# laserBordMain.net
KiCad netlist of a schematic drawn in EasyEDA Pro
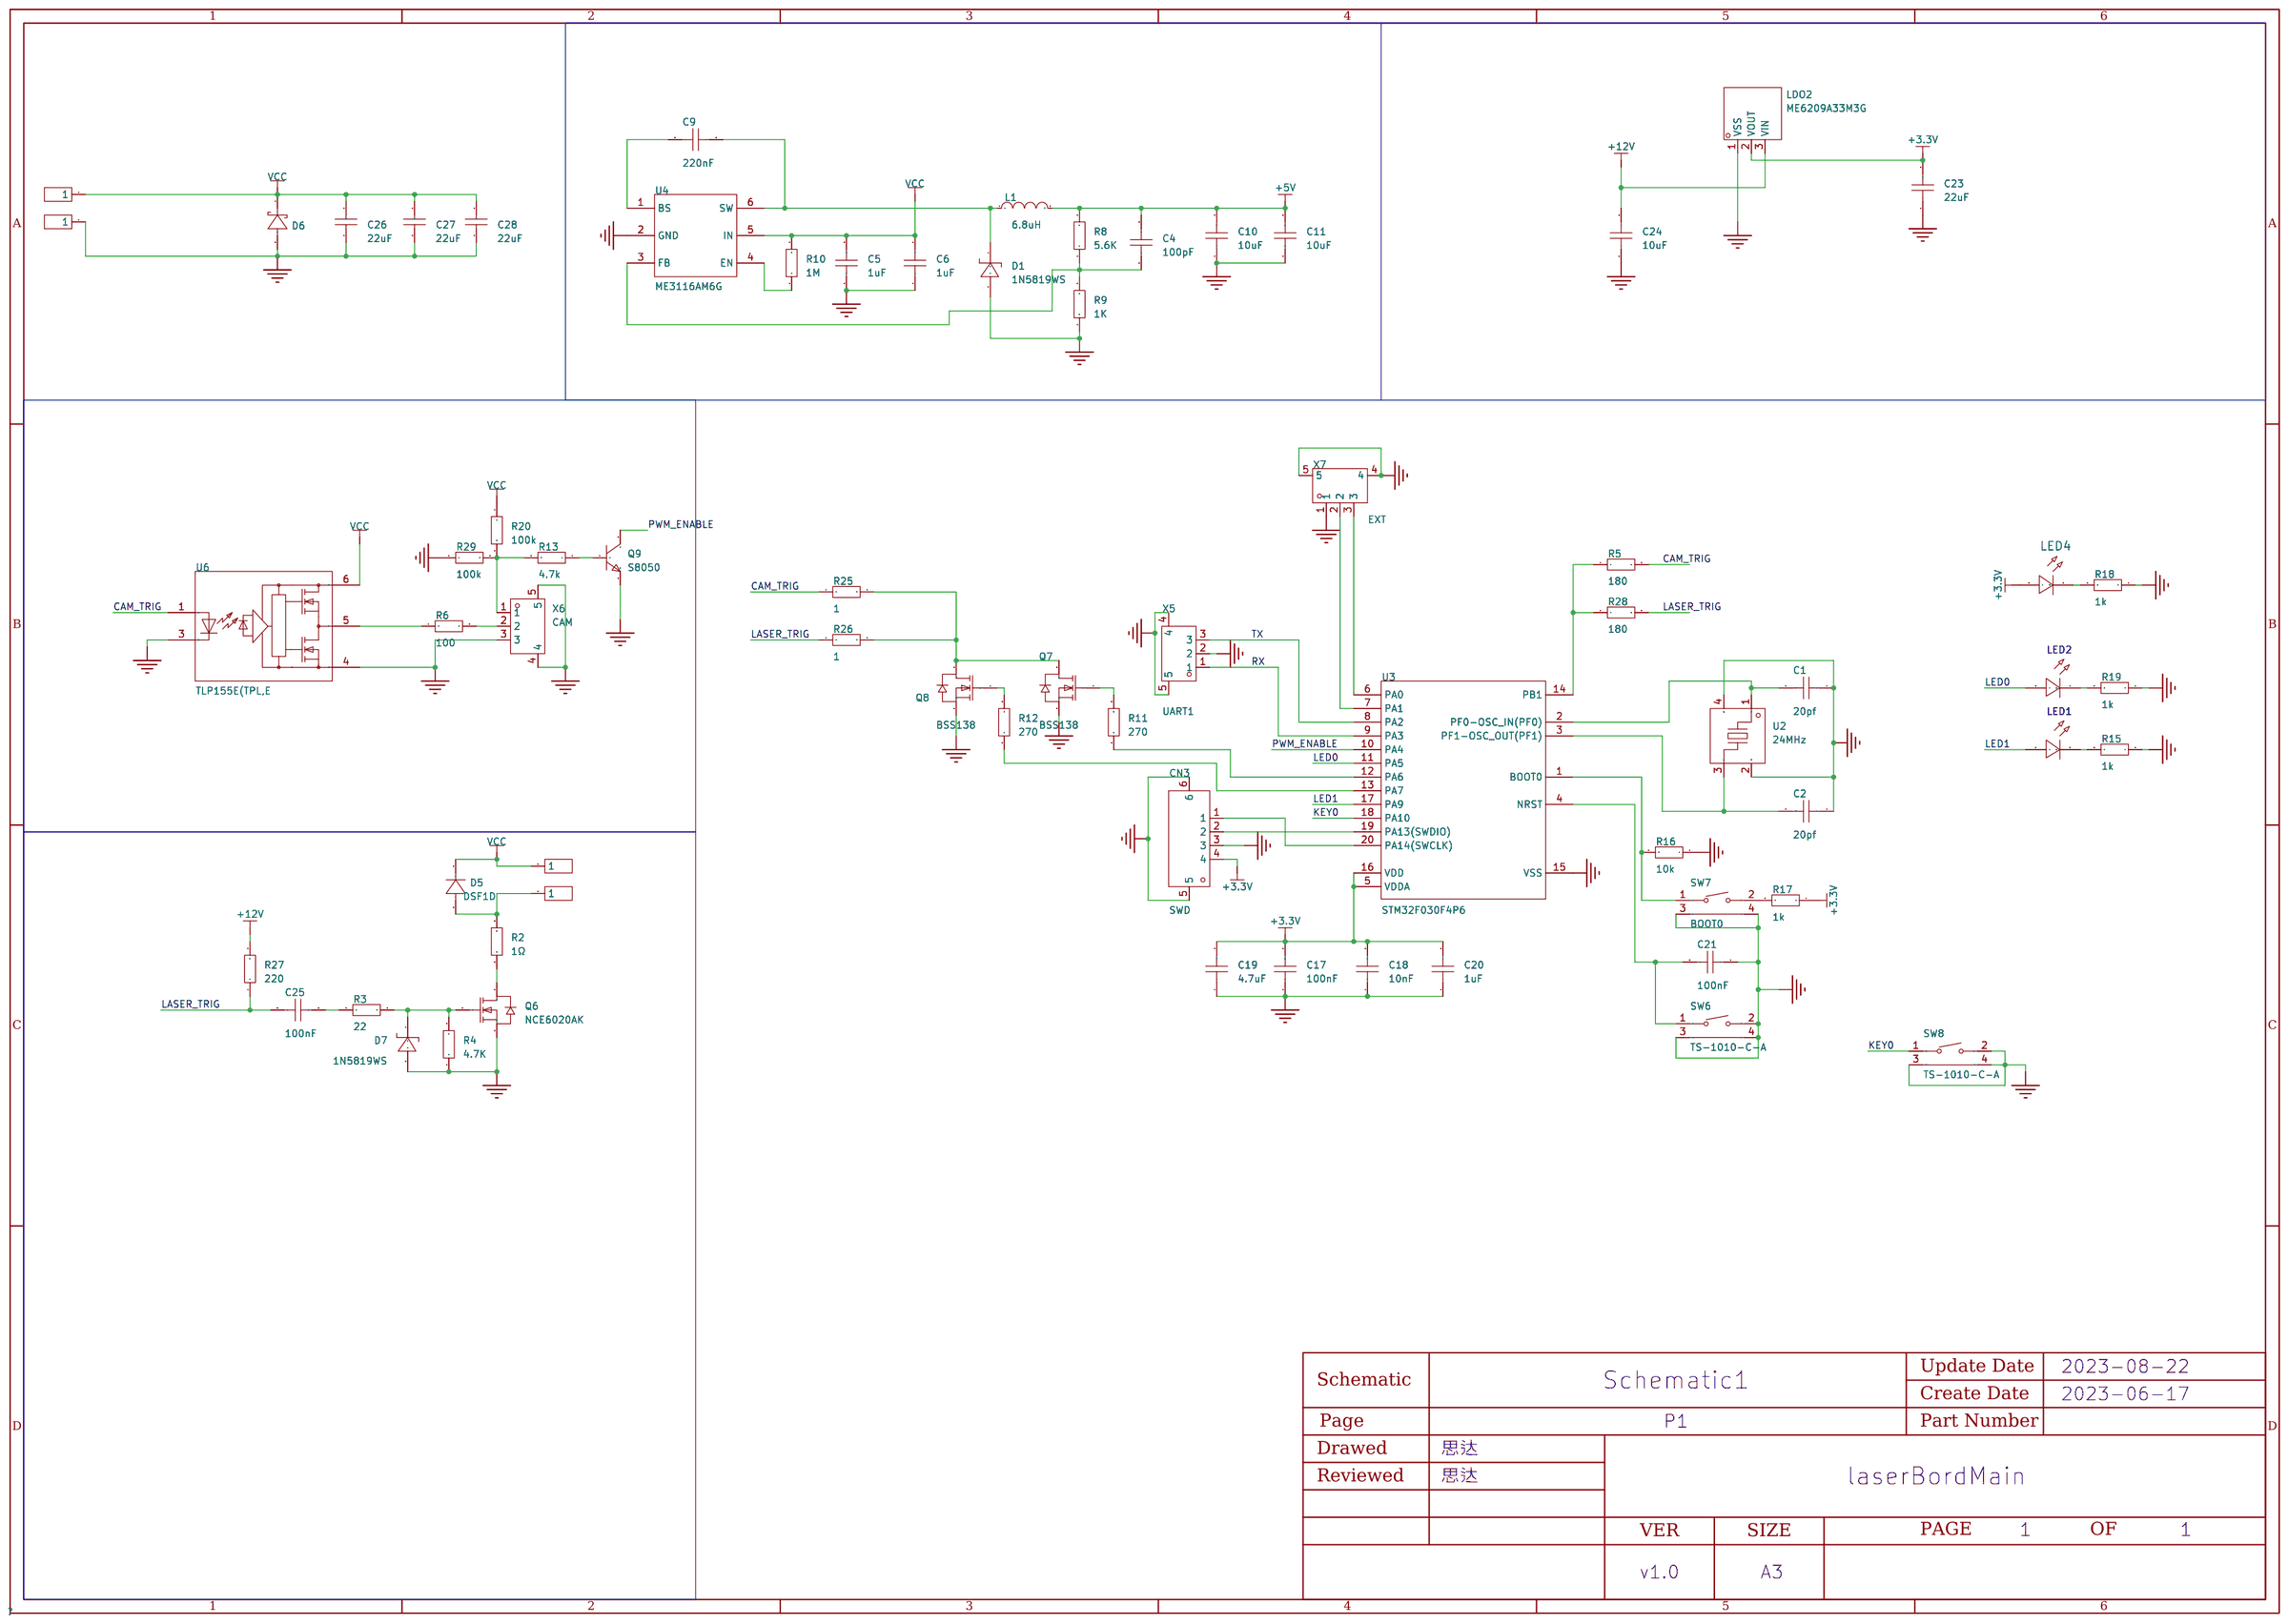
[diagram p0: schematic sheet]

(export (version "E")
  (design (tool "Eeschema 10.0.6"))
  (components
    (comp (ref "C1")
      (value "20pf")
      (footprint "easyedapro:C0603")
      (libsource (lib "easyedapro") (part "CapAcitance"))
    )
    (comp (ref "C2")
      (value "20pf")
      (footprint "easyedapro:C0603")
      (libsource (lib "easyedapro") (part "CapAcitance"))
    )
    (comp (ref "C4")
      (value "100pF")
      (footprint "easyedapro:C0603")
      (libsource (lib "easyedapro") (part "CapAcitance"))
    )
    (comp (ref "C5")
      (value "1uF")
      (footprint "easyedapro:C0603")
      (libsource (lib "easyedapro") (part "CapAcitance"))
    )
    (comp (ref "C6")
      (value "1uF")
      (footprint "easyedapro:C0603")
      (libsource (lib "easyedapro") (part "CapAcitance"))
    )
    (comp (ref "C9")
      (value "220nF")
      (footprint "easyedapro:C0603")
      (libsource (lib "easyedapro") (part "CapAcitance"))
    )
    (comp (ref "C10")
      (value "10uF")
      (footprint "easyedapro:C0603")
      (libsource (lib "easyedapro") (part "CapAcitance"))
    )
    (comp (ref "C11")
      (value "10uF")
      (footprint "easyedapro:C0603")
      (libsource (lib "easyedapro") (part "CapAcitance"))
    )
    (comp (ref "C17")
      (value "100nF")
      (footprint "easyedapro:C0603")
      (libsource (lib "easyedapro") (part "CapAcitance"))
    )
    (comp (ref "C18")
      (value "10nF")
      (footprint "easyedapro:C0603")
      (libsource (lib "easyedapro") (part "CapAcitance"))
    )
    (comp (ref "C19")
      (value "4.7uF")
      (footprint "easyedapro:C0603")
      (libsource (lib "easyedapro") (part "CapAcitance"))
    )
    (comp (ref "C20")
      (value "1uF")
      (footprint "easyedapro:C0603")
      (libsource (lib "easyedapro") (part "CapAcitance"))
    )
    (comp (ref "C21")
      (value "100nF")
      (footprint "easyedapro:C0603")
      (libsource (lib "easyedapro") (part "CapAcitance"))
    )
    (comp (ref "C23")
      (value "22uF")
      (footprint "easyedapro:C0603")
      (libsource (lib "easyedapro") (part "CapAcitance"))
    )
    (comp (ref "C24")
      (value "10uF")
      (footprint "easyedapro:C0603")
      (libsource (lib "easyedapro") (part "CapAcitance"))
    )
    (comp (ref "C25")
      (value "100nF")
      (footprint "easyedapro:C0603")
      (libsource (lib "easyedapro") (part "CapAcitance"))
    )
    (comp (ref "C26")
      (value "22uF")
      (footprint "easyedapro:C1210")
      (description "容值:10uF;精度:±10%;额定电压:25V;材质(温度系数):X7R;")
      (fields
        (field (name "Manufacturer Part") "GRM32DR71E106KA12L")
        (field (name "Manufacturer") "muRata(村田)")
      )
      (libsource (lib "easyedapro") (part "GRM32DR71E106KA12L"))
    )
    (comp (ref "C27")
      (value "22uF")
      (footprint "easyedapro:C1210")
      (description "容值:10uF;精度:±10%;额定电压:25V;材质(温度系数):X7R;")
      (fields
        (field (name "Manufacturer Part") "GRM32DR71E106KA12L")
        (field (name "Manufacturer") "muRata(村田)")
      )
      (libsource (lib "easyedapro") (part "GRM32DR71E106KA12L"))
    )
    (comp (ref "C28")
      (value "22uF")
      (footprint "easyedapro:C1210")
      (description "容值:10uF;精度:±10%;额定电压:25V;材质(温度系数):X7R;")
      (fields
        (field (name "Manufacturer Part") "GRM32DR71E106KA12L")
        (field (name "Manufacturer") "muRata(村田)")
      )
      (libsource (lib "easyedapro") (part "GRM32DR71E106KA12L"))
    )
    (comp (ref "CN3")
      (value "SWD")
      (footprint "easyedapro:CONN-SMD_4P-P1.27_GH125-S04DCA-00")
      (description "参考系列:-;间距:1.25mm;插针结构:1x4P;排数:1;每排PIN数:4;行距:-;公母:公型插针;安装方式:卧贴;额定电流:1A;工作温度范围:-25°C~+85°C;")
      (fields (field (name "Manufacturer") "JS(钜硕电子)"))
      (libsource (lib "easyedapro") (part "GH125-S04DCA-00"))
    )
    (comp (ref "D1")
      (value "1N5819WS")
      (footprint "easyedapro:SOD-323_L1.8-W1.3-LS2.5-RD")
      (description "直流反向耐压(Vr):40V;平均整流电流(Io):1A;正向压降(Vf):600mV@1A;")
      (fields (field (name "Manufacturer") "Hottech(合科泰)"))
      (libsource (lib "easyedapro") (part "1N5819WS"))
    )
    (comp (ref "D5")
      (value "DSF1D")
      (footprint "easyedapro:SOD-123_L2.8-W1.8-LS3.7-RD")
      (description "二极管配置:独立式;直流反向耐压(Vr):200V;平均整流电流(Io):1A;正向压降(Vf):950mV@1A;反向恢复时间(trr):35ns;")
      (fields (field (name "Manufacturer") "FUXINSEMI(富芯森美)"))
      (libsource (lib "easyedapro") (part "DSF1D_C915614"))
    )
    (comp (ref "D6")
      (value "SMAJ28A")
      (footprint "easyedapro:D-FLAT_L4.3-W2.6-LS5.3-RD")
      (fields (field (name "Manufacturer") "CJ(江苏长电/长晶)"))
      (libsource (lib "easyedapro") (part "SMAJ28A_C1509532"))
    )
    (comp (ref "D7")
      (value "1N5819WS")
      (footprint "easyedapro:SOD-323_L1.8-W1.3-LS2.5-RD")
      (description "直流反向耐压(Vr):40V;平均整流电流(Io):1A;正向压降(Vf):600mV@1A;")
      (fields (field (name "Manufacturer") "Hottech(合科泰)"))
      (libsource (lib "easyedapro") (part "1N5819WS"))
    )
    (comp (ref "H1")
      (value "~")
      (footprint "easyedapro:HDR-TH_1P-V-M_XKB_X4611WV-01I-C28D40")
      (libsource (lib "easyedapro") (part "HDR_1x1"))
    )
    (comp (ref "H2")
      (value "~")
      (footprint "easyedapro:HDR-TH_1P-V-M_XKB_X4611WV-01I-C28D40")
      (libsource (lib "easyedapro") (part "HDR_1x1"))
    )
    (comp (ref "H3")
      (value "~")
      (footprint "easyedapro:HDR-TH_1P-V-M_XKB_X4611WV-01I-C28D40")
      (libsource (lib "easyedapro") (part "HDR_1x1"))
    )
    (comp (ref "H4")
      (value "~")
      (footprint "easyedapro:HDR-TH_1P-V-M_XKB_X4611WV-01I-C28D40")
      (libsource (lib "easyedapro") (part "HDR_1x1"))
    )
    (comp (ref "L1")
      (value "6.8uH")
      (footprint "easyedapro:L1206")
      (libsource (lib "easyedapro") (part "CMI321609VR27KT"))
    )
    (comp (ref "LDO2")
      (value "ME6209A33M3G")
      (footprint "easyedapro:SOT-23-3_L2.9-W1.6-P1.90-LS2.8-BR")
      (description "输出类型:固定;输出极性:正;最大输入电压:18V;输出电压:3.3V;输出电流:250mA;电源纹波抑制比(PSRR):-;")
      (fields (field (name "Manufacturer") "MICRONE(南京微盟)"))
      (libsource (lib "easyedapro") (part "ME6209A33M3G"))
    )
    (comp (ref "LED1")
      (value "~")
      (footprint "easyedapro:LED_0603")
      (libsource (lib "easyedapro") (part "LED_B"))
    )
    (comp (ref "LED2")
      (value "~")
      (footprint "easyedapro:LED_0603")
      (libsource (lib "easyedapro") (part "LED_B"))
    )
    (comp (ref "LED4")
      (value "~")
      (footprint "easyedapro:LED_0603")
      (libsource (lib "easyedapro") (part "LED_R"))
    )
    (comp (ref "Q6")
      (value "NCE6020AK")
      (footprint "easyedapro:TO-252-2_L6.6-W6.1-P4.57-LS10.1-TL-CW")
      (fields (field (name "Manufacturer") "NCE(无锡新洁能)"))
      (libsource (lib "easyedapro") (part "NCE6020AK"))
    )
    (comp (ref "Q7")
      (value "BSS138")
      (footprint "easyedapro:SOT-23-3_L2.9-W1.3-P1.90-LS2.4-BR")
      (description "类型:N沟道;漏源电压(Vdss):50V;连续漏极电流(Id):220mA;功率(Pd):360mW;导通电阻(RDS(on)@Vgs,Id):3.5Ω@10V,220mA;")
      (fields (field (name "Manufacturer") "CJ(江苏长电/长晶)"))
      (libsource (lib "easyedapro") (part "BSS138"))
    )
    (comp (ref "Q8")
      (value "BSS138")
      (footprint "easyedapro:SOT-23-3_L2.9-W1.3-P1.90-LS2.4-BR")
      (description "类型:N沟道;漏源电压(Vdss):50V;连续漏极电流(Id):220mA;功率(Pd):360mW;导通电阻(RDS(on)@Vgs,Id):3.5Ω@10V,220mA;")
      (fields (field (name "Manufacturer") "CJ(江苏长电/长晶)"))
      (libsource (lib "easyedapro") (part "BSS138"))
    )
    (comp (ref "Q9")
      (value "S8050")
      (footprint "easyedapro:SOT-23-3_L2.9-W1.6-P1.90-LS2.8-BR")
      (description "晶体管类型:NPN;集射极击穿电压(Vceo):25V;集电极电流(Ic):500mA;功率(Pd):300mW;直流电流增益(hFE@Ic,Vce):120@50mA,1V;")
      (fields (field (name "Manufacturer") "CJ(江苏长电/长晶)"))
      (libsource (lib "easyedapro") (part "S8050_C105433"))
    )
    (comp (ref "R2")
      (value "1Ω")
      (footprint "easyedapro:R2010")
      (description "电阻类型:厚膜电阻;阻值:0Ω;精度:±5%;功率:750mW;")
      (fields
        (field (name "Manufacturer Part") "201007J0000T4E")
        (field (name "Manufacturer") "UNI-ROYAL(厚声)")
      )
      (libsource (lib "easyedapro") (part "201007J0000T4E"))
    )
    (comp (ref "R3") (value "22") (footprint "easyedapro:R0603") (libsource (lib "easyedapro") (part "电阻")))
    (comp (ref "R4") (value "4.7K") (footprint "easyedapro:R0603") (libsource (lib "easyedapro") (part "电阻")))
    (comp (ref "R5") (value "180") (footprint "easyedapro:R0603") (libsource (lib "easyedapro") (part "电阻")))
    (comp (ref "R6") (value "100") (footprint "easyedapro:R0603") (libsource (lib "easyedapro") (part "电阻")))
    (comp (ref "R8") (value "5.6K") (footprint "easyedapro:R0603") (libsource (lib "easyedapro") (part "电阻")))
    (comp (ref "R9") (value "1K") (footprint "easyedapro:R0603") (libsource (lib "easyedapro") (part "电阻")))
    (comp (ref "R10") (value "1M") (footprint "easyedapro:R0603") (libsource (lib "easyedapro") (part "电阻")))
    (comp (ref "R11") (value "270") (footprint "easyedapro:R0603") (libsource (lib "easyedapro") (part "电阻")))
    (comp (ref "R12") (value "270") (footprint "easyedapro:R0603") (libsource (lib "easyedapro") (part "电阻")))
    (comp (ref "R13")
      (value "4.7k")
      (footprint "easyedapro:R0603")
      (libsource (lib "easyedapro") (part "电阻"))
    )
    (comp (ref "R15") (value "1k") (footprint "easyedapro:R0603") (libsource (lib "easyedapro") (part "电阻")))
    (comp (ref "R16") (value "10k") (footprint "easyedapro:R0603") (libsource (lib "easyedapro") (part "电阻")))
    (comp (ref "R17") (value "1k") (footprint "easyedapro:R0603") (libsource (lib "easyedapro") (part "电阻")))
    (comp (ref "R18") (value "1k") (footprint "easyedapro:R0603") (libsource (lib "easyedapro") (part "电阻")))
    (comp (ref "R19") (value "1k") (footprint "easyedapro:R0603") (libsource (lib "easyedapro") (part "电阻")))
    (comp (ref "R20")
      (value "100k")
      (footprint "easyedapro:R0603")
      (libsource (lib "easyedapro") (part "电阻"))
    )
    (comp (ref "R25") (value "1") (footprint "easyedapro:R0603") (libsource (lib "easyedapro") (part "电阻")))
    (comp (ref "R26") (value "1") (footprint "easyedapro:R0603") (libsource (lib "easyedapro") (part "电阻")))
    (comp (ref "R27") (value "220") (footprint "easyedapro:R0603") (libsource (lib "easyedapro") (part "电阻")))
    (comp (ref "R28") (value "180") (footprint "easyedapro:R0603") (libsource (lib "easyedapro") (part "电阻")))
    (comp (ref "R29")
      (value "100k")
      (footprint "easyedapro:R0603")
      (libsource (lib "easyedapro") (part "电阻"))
    )
    (comp (ref "SW6")
      (value "TS-1010-C-A")
      (footprint "easyedapro:KEY-SMD_TX-1010-X-X")
      (description "触点电流:50mA;额定电压(DC):12V;绝缘电阻:-;电路结构:单刀单掷;安装方式:卧贴;带灯:无;作用力:260gf;机械寿命:10万次;带支架:否;")
      (fields (field (name "Manufacturer") "XKB Connectivity(中国星坤)"))
      (libsource (lib "easyedapro") (part "TS-1010-C-A"))
    )
    (comp (ref "SW7")
      (value "BOOT0")
      (footprint "easyedapro:KEY-SMD_TX-1010-X-X")
      (description "触点电流:50mA;额定电压(DC):12V;绝缘电阻:-;电路结构:单刀单掷;安装方式:卧贴;带灯:无;作用力:260gf;机械寿命:10万次;带支架:否;")
      (fields (field (name "Manufacturer") "XKB Connectivity(中国星坤)"))
      (libsource (lib "easyedapro") (part "TS-1010-C-A"))
    )
    (comp (ref "SW8")
      (value "TS-1010-C-A")
      (footprint "easyedapro:KEY-SMD_TX-1010-X-X")
      (description "触点电流:50mA;额定电压(DC):12V;绝缘电阻:-;电路结构:单刀单掷;安装方式:卧贴;带灯:无;作用力:260gf;机械寿命:10万次;带支架:否;")
      (fields (field (name "Manufacturer") "XKB Connectivity(中国星坤)"))
      (libsource (lib "easyedapro") (part "TS-1010-C-A"))
    )
    (comp (ref "U2")
      (value "24MHz")
      (footprint "easyedapro:CRYSTAL-SMD_4P-L3.2-W2.5-BL")
      (description "频率:24MHz;频率公差:±20ppm;负载电容:20pF;")
      (fields
        (field (name "Manufacturer Part") "XXHCCLNANF-24MHZ")
        (field (name "Manufacturer") "TAITIEN(泰艺电子)")
      )
      (libsource (lib "easyedapro") (part "XXHCCLNANF-24MHZ"))
    )
    (comp (ref "U3")
      (value "STM32F030F4P6")
      (footprint "easyedapro:TSSOP-20_L6.5-W4.4-P0.65-LS6.4-BL")
      (description "CPU内核:ARM Cortex-M0;CPU最大主频:48MHz;程序存储容量:16KB;程序存储器类型:FLASH;RAM总容量:4KB;GPIO端口数量:15;")
      (fields (field (name "Manufacturer") "ST(意法半导体)"))
      (libsource (lib "easyedapro") (part "STM32F030F4P6"))
    )
    (comp (ref "U4")
      (value "ME3116AM6G")
      (footprint "easyedapro:SOT-23-6_L2.9-W1.6-P0.95-LS2.8-BL")
      (description "功能类型:降压型;同步整流:-;输出通道数:-;拓扑结构:-;输入电压:-;输出电流(最大值):-;开关频率:-;")
      (fields (field (name "Manufacturer") "MICRONE(南京微盟)"))
      (libsource (lib "easyedapro") (part "ME3116"))
    )
    (comp (ref "U6")
      (value "TLP155E(TPL,E")
      (footprint "easyedapro:OPTO-SMD-5_L3.7-W4.6-P1.27-LS7.0-BR")
      (fields (field (name "Manufacturer") "TOSHIBA(东芝)"))
      (libsource (lib "easyedapro") (part "TLP155E(TPL,E"))
    )
    (comp (ref "X5")
      (value "UART1")
      (footprint "easyedapro:CONN-SMD_3P-P1.25_JUSHUO_GH125-S03DCA-00")
      (description "参考系列:-;间距:1.25mm;插针结构:1x3P;排数:1;每排PIN数:3;行距:-;公母:公型插针;安装方式:卧贴;额定电流:1A;工作温度范围:-25°C~+85°C;")
      (fields (field (name "Manufacturer") "JS(钜硕电子)"))
      (libsource (lib "easyedapro") (part "GH125-S03DCA-00"))
    )
    (comp (ref "X6")
      (value "CAM")
      (footprint "easyedapro:CONN-SMD_3P-P1.25_JUSHUO_GH125-S03DCA-00")
      (description "参考系列:-;间距:1.25mm;插针结构:1x3P;排数:1;每排PIN数:3;行距:-;公母:公型插针;安装方式:卧贴;额定电流:1A;工作温度范围:-25°C~+85°C;")
      (fields (field (name "Manufacturer") "JS(钜硕电子)"))
      (libsource (lib "easyedapro") (part "GH125-S03DCA-00"))
    )
    (comp (ref "X7")
      (value "EXT")
      (footprint "easyedapro:CONN-SMD_3P-P1.25_JUSHUO_GH125-S03DCA-00")
      (description "参考系列:-;间距:1.25mm;插针结构:1x3P;排数:1;每排PIN数:3;行距:-;公母:公型插针;安装方式:卧贴;额定电流:1A;工作温度范围:-25°C~+85°C;")
      (fields (field (name "Manufacturer") "JS(钜硕电子)"))
      (libsource (lib "easyedapro") (part "GH125-S03DCA-00"))
    )
  )
  (nets
    (net (code "1") (name "+3.3V") (class "Default")
      (node (ref "C17") (pin "2") (pinfunction "2_2") (pintype "input"))
      (node (ref "C18") (pin "2") (pinfunction "2_2") (pintype "input"))
      (node (ref "C19") (pin "2") (pinfunction "2_2") (pintype "input"))
      (node (ref "C20") (pin "2") (pinfunction "2_2") (pintype "input"))
      (node (ref "C23") (pin "2") (pinfunction "2_2") (pintype "input"))
      (node (ref "CN3") (pin "4") (pinfunction "4_4") (pintype "input"))
      (node (ref "LDO2") (pin "2") (pinfunction "VOUT_2") (pintype "input"))
      (node (ref "LED4") (pin "2") (pinfunction "A_2") (pintype "input"))
      (node (ref "R17") (pin "1") (pinfunction "1_1") (pintype "input"))
      (node (ref "U3") (pin "16") (pinfunction "VDD_16") (pintype "input"))
      (node (ref "U3") (pin "5") (pinfunction "VDDA_5") (pintype "input"))
    )
    (net (code "2") (name "+5V") (class "Default")
      (node (ref "C10") (pin "2") (pinfunction "2_2") (pintype "input"))
      (node (ref "C11") (pin "2") (pinfunction "2_2") (pintype "input"))
      (node (ref "C4") (pin "2") (pinfunction "2_2") (pintype "input"))
      (node (ref "L1") (pin "2") (pinfunction "2_2") (pintype "input"))
      (node (ref "R8") (pin "2") (pinfunction "2_2") (pintype "input"))
    )
    (net (code "3") (name "+12V") (class "Default")
      (node (ref "C24") (pin "2") (pinfunction "2_2") (pintype "input"))
      (node (ref "LDO2") (pin "3") (pinfunction "VIN_3") (pintype "input"))
      (node (ref "R27") (pin "2") (pinfunction "2_2") (pintype "input"))
    )
    (net (code "4") (name "/CAM_TRIG") (class "Default")
      (node (ref "R25") (pin "1") (pinfunction "1_1") (pintype "input"))
      (node (ref "R5") (pin "2") (pinfunction "2_2") (pintype "input"))
      (node (ref "U6") (pin "1") (pinfunction "AN_1") (pintype "input"))
    )
    (net (code "5") (name "/KEY0") (class "Default")
      (node (ref "SW8") (pin "1") (pinfunction "1_1") (pintype "input"))
      (node (ref "U3") (pin "18") (pinfunction "PA10_18") (pintype "bidirectional"))
    )
    (net (code "6") (name "/LASER_TRIG") (class "Default")
      (node (ref "C25") (pin "1") (pinfunction "1_1") (pintype "input"))
      (node (ref "R26") (pin "1") (pinfunction "1_1") (pintype "input"))
      (node (ref "R27") (pin "1") (pinfunction "1_1") (pintype "input"))
      (node (ref "R28") (pin "2") (pinfunction "2_2") (pintype "input"))
    )
    (net (code "7") (name "/LED0") (class "Default")
      (node (ref "LED2") (pin "2") (pinfunction "A_2") (pintype "input"))
      (node (ref "U3") (pin "11") (pinfunction "PA5_11") (pintype "bidirectional"))
    )
    (net (code "8") (name "/LED1") (class "Default")
      (node (ref "LED1") (pin "2") (pinfunction "A_2") (pintype "input"))
      (node (ref "U3") (pin "17") (pinfunction "PA9_17") (pintype "bidirectional"))
    )
    (net (code "9") (name "/PWM_ENABLE") (class "Default")
      (node (ref "Q9") (pin "3") (pinfunction "3_3") (pintype "input"))
      (node (ref "U3") (pin "10") (pinfunction "PA4_10") (pintype "bidirectional"))
    )
    (net (code "10") (name "/RX") (class "Default")
      (node (ref "U3") (pin "9") (pinfunction "PA3_9") (pintype "bidirectional"))
      (node (ref "X5") (pin "1") (pinfunction "1_1") (pintype "input"))
    )
    (net (code "11") (name "/TX") (class "Default")
      (node (ref "U3") (pin "8") (pinfunction "PA2_8") (pintype "bidirectional"))
      (node (ref "X5") (pin "3") (pinfunction "3_3") (pintype "input"))
    )
    (net (code "12") (name "GND") (class "Default")
      (node (ref "C1") (pin "1") (pinfunction "1_1") (pintype "input"))
      (node (ref "C10") (pin "1") (pinfunction "1_1") (pintype "input"))
      (node (ref "C11") (pin "1") (pinfunction "1_1") (pintype "input"))
      (node (ref "C17") (pin "1") (pinfunction "1_1") (pintype "input"))
      (node (ref "C18") (pin "1") (pinfunction "1_1") (pintype "input"))
      (node (ref "C19") (pin "1") (pinfunction "1_1") (pintype "input"))
      (node (ref "C2") (pin "1") (pinfunction "1_1") (pintype "input"))
      (node (ref "C20") (pin "1") (pinfunction "1_1") (pintype "input"))
      (node (ref "C21") (pin "1") (pinfunction "1_1") (pintype "input"))
      (node (ref "C23") (pin "1") (pinfunction "1_1") (pintype "input"))
      (node (ref "C24") (pin "1") (pinfunction "1_1") (pintype "input"))
      (node (ref "C26") (pin "1") (pinfunction "1_1") (pintype "input"))
      (node (ref "C27") (pin "1") (pinfunction "1_1") (pintype "input"))
      (node (ref "C28") (pin "1") (pinfunction "1_1") (pintype "input"))
      (node (ref "C5") (pin "1") (pinfunction "1_1") (pintype "input"))
      (node (ref "C6") (pin "1") (pinfunction "1_1") (pintype "input"))
      (node (ref "CN3") (pin "3") (pinfunction "3_3") (pintype "input"))
      (node (ref "CN3") (pin "5") (pinfunction "5_5") (pintype "input"))
      (node (ref "CN3") (pin "6") (pinfunction "6_6") (pintype "input"))
      (node (ref "D1") (pin "2") (pinfunction "A_2") (pintype "input"))
      (node (ref "D6") (pin "2") (pinfunction "K_2") (pintype "input"))
      (node (ref "D7") (pin "2") (pinfunction "A_2") (pintype "input"))
      (node (ref "H2") (pin "1") (pinfunction "1_1") (pintype "unspecified"))
      (node (ref "LDO2") (pin "1") (pinfunction "VSS_1") (pintype "input"))
      (node (ref "Q6") (pin "3") (pinfunction "S_3") (pintype "input"))
      (node (ref "Q7") (pin "2") (pinfunction "S_2") (pintype "input"))
      (node (ref "Q8") (pin "2") (pinfunction "S_2") (pintype "input"))
      (node (ref "Q9") (pin "2") (pinfunction "2_2") (pintype "input"))
      (node (ref "R15") (pin "1") (pinfunction "1_1") (pintype "input"))
      (node (ref "R16") (pin "1") (pinfunction "1_1") (pintype "input"))
      (node (ref "R18") (pin "1") (pinfunction "1_1") (pintype "input"))
      (node (ref "R19") (pin "1") (pinfunction "1_1") (pintype "input"))
      (node (ref "R29") (pin "1") (pinfunction "1_1") (pintype "input"))
      (node (ref "R4") (pin "1") (pinfunction "1_1") (pintype "input"))
      (node (ref "R9") (pin "1") (pinfunction "1_1") (pintype "input"))
      (node (ref "SW6") (pin "2") (pinfunction "2_2") (pintype "input"))
      (node (ref "SW6") (pin "3") (pinfunction "3_3") (pintype "input"))
      (node (ref "SW6") (pin "4") (pinfunction "4_4") (pintype "input"))
      (node (ref "SW7") (pin "3") (pinfunction "3_3") (pintype "input"))
      (node (ref "SW7") (pin "4") (pinfunction "4_4") (pintype "input"))
      (node (ref "SW8") (pin "2") (pinfunction "2_2") (pintype "input"))
      (node (ref "SW8") (pin "3") (pinfunction "3_3") (pintype "input"))
      (node (ref "SW8") (pin "4") (pinfunction "4_4") (pintype "input"))
      (node (ref "U2") (pin "2") (pinfunction "GND_2") (pintype "input"))
      (node (ref "U2") (pin "4") (pinfunction "GND_4") (pintype "input"))
      (node (ref "U3") (pin "15") (pinfunction "VSS_15") (pintype "input"))
      (node (ref "U4") (pin "2") (pinfunction "GND_2") (pintype "input"))
      (node (ref "U6") (pin "3") (pinfunction "CAT_3") (pintype "input"))
      (node (ref "U6") (pin "4") (pinfunction "GND_4") (pintype "input"))
      (node (ref "X5") (pin "2") (pinfunction "2_2") (pintype "input"))
      (node (ref "X5") (pin "4") (pinfunction "4_4") (pintype "input"))
      (node (ref "X5") (pin "5") (pinfunction "5_5") (pintype "input"))
      (node (ref "X6") (pin "3") (pinfunction "3_3") (pintype "input"))
      (node (ref "X6") (pin "4") (pinfunction "4_4") (pintype "input"))
      (node (ref "X6") (pin "5") (pinfunction "5_5") (pintype "input"))
      (node (ref "X7") (pin "1") (pinfunction "1_1") (pintype "input"))
      (node (ref "X7") (pin "4") (pinfunction "4_4") (pintype "input"))
      (node (ref "X7") (pin "5") (pinfunction "5_5") (pintype "input"))
    )
    (net (code "13") (name "Net-(C25-Pad2)") (class "Default")
      (node (ref "C25") (pin "2") (pinfunction "2_2") (pintype "input"))
      (node (ref "R3") (pin "1") (pinfunction "1_1") (pintype "input"))
    )
    (net (code "14") (name "Net-(D1-C)") (class "Default")
      (node (ref "C9") (pin "2") (pinfunction "2_2") (pintype "input"))
      (node (ref "D1") (pin "1") (pinfunction "C_1") (pintype "input"))
      (node (ref "L1") (pin "1") (pinfunction "1_1") (pintype "input"))
      (node (ref "U4") (pin "6") (pinfunction "SW_6") (pintype "input"))
    )
    (net (code "15") (name "Net-(D5-A)") (class "Default")
      (node (ref "D5") (pin "2") (pinfunction "A_2") (pintype "input"))
      (node (ref "H4") (pin "1") (pinfunction "1_1") (pintype "unspecified"))
      (node (ref "R2") (pin "2") (pinfunction "2_2") (pintype "input"))
    )
    (net (code "16") (name "Net-(D7-C)") (class "Default")
      (node (ref "D7") (pin "1") (pinfunction "C_1") (pintype "input"))
      (node (ref "Q6") (pin "1") (pinfunction "G_1") (pintype "input"))
      (node (ref "R3") (pin "2") (pinfunction "2_2") (pintype "input"))
      (node (ref "R4") (pin "2") (pinfunction "2_2") (pintype "input"))
    )
    (net (code "17") (name "Net-(LED1-C)") (class "Default")
      (node (ref "LED1") (pin "1") (pinfunction "C_1") (pintype "input"))
      (node (ref "R15") (pin "2") (pinfunction "2_2") (pintype "input"))
    )
    (net (code "18") (name "Net-(LED2-C)") (class "Default")
      (node (ref "LED2") (pin "1") (pinfunction "C_1") (pintype "input"))
      (node (ref "R19") (pin "2") (pinfunction "2_2") (pintype "input"))
    )
    (net (code "19") (name "Net-(LED4-C)") (class "Default")
      (node (ref "LED4") (pin "1") (pinfunction "C_1") (pintype "input"))
      (node (ref "R18") (pin "2") (pinfunction "2_2") (pintype "input"))
    )
    (net (code "20") (name "Net-(Q6-D)") (class "Default")
      (node (ref "Q6") (pin "2") (pinfunction "D_2") (pintype "input"))
      (node (ref "R2") (pin "1") (pinfunction "1_1") (pintype "input"))
    )
    (net (code "21") (name "Net-(Q7-D)") (class "Default")
      (node (ref "Q7") (pin "3") (pinfunction "D_3") (pintype "input"))
      (node (ref "Q8") (pin "3") (pinfunction "D_3") (pintype "input"))
      (node (ref "R25") (pin "2") (pinfunction "2_2") (pintype "input"))
      (node (ref "R26") (pin "2") (pinfunction "2_2") (pintype "input"))
    )
    (net (code "22") (name "Net-(Q7-G)") (class "Default")
      (node (ref "Q7") (pin "1") (pinfunction "G_1") (pintype "input"))
      (node (ref "R11") (pin "2") (pinfunction "2_2") (pintype "input"))
    )
    (net (code "23") (name "Net-(Q8-G)") (class "Default")
      (node (ref "Q8") (pin "1") (pinfunction "G_1") (pintype "input"))
      (node (ref "R12") (pin "2") (pinfunction "2_2") (pintype "input"))
    )
    (net (code "24") (name "Net-(Q9-Pad1)") (class "Default")
      (node (ref "Q9") (pin "1") (pinfunction "1_1") (pintype "input"))
      (node (ref "R13") (pin "1") (pinfunction "1_1") (pintype "input"))
    )
    (net (code "25") (name "Net-(R6-Pad2)") (class "Default")
      (node (ref "R6") (pin "2") (pinfunction "2_2") (pintype "input"))
      (node (ref "X6") (pin "2") (pinfunction "2_2") (pintype "input"))
    )
    (net (code "26") (name "Net-(R13-Pad2)") (class "Default")
      (node (ref "R13") (pin "2") (pinfunction "2_2") (pintype "input"))
      (node (ref "R20") (pin "2") (pinfunction "2_2") (pintype "input"))
      (node (ref "R29") (pin "2") (pinfunction "2_2") (pintype "input"))
      (node (ref "X6") (pin "1") (pinfunction "1_1") (pintype "input"))
    )
    (net (code "27") (name "Net-(R17-Pad2)") (class "Default")
      (node (ref "R17") (pin "2") (pinfunction "2_2") (pintype "input"))
      (node (ref "SW7") (pin "2") (pinfunction "2_2") (pintype "input"))
    )
    (net (code "28") (name "Net-(U3-BOOT0)") (class "Default")
      (node (ref "R16") (pin "2") (pinfunction "2_2") (pintype "input"))
      (node (ref "SW7") (pin "1") (pinfunction "1_1") (pintype "input"))
      (node (ref "U3") (pin "1") (pinfunction "BOOT0_1") (pintype "input"))
    )
    (net (code "29") (name "Net-(U3-NRST)") (class "Default")
      (node (ref "C21") (pin "2") (pinfunction "2_2") (pintype "input"))
      (node (ref "SW6") (pin "1") (pinfunction "1_1") (pintype "input"))
      (node (ref "U3") (pin "4") (pinfunction "NRST_4") (pintype "bidirectional"))
    )
    (net (code "30") (name "Net-(U3-PA0)") (class "Default")
      (node (ref "U3") (pin "6") (pinfunction "PA0_6") (pintype "bidirectional"))
      (node (ref "X7") (pin "3") (pinfunction "3_3") (pintype "input"))
    )
    (net (code "31") (name "Net-(U3-PA1)") (class "Default")
      (node (ref "U3") (pin "7") (pinfunction "PA1_7") (pintype "bidirectional"))
      (node (ref "X7") (pin "2") (pinfunction "2_2") (pintype "input"))
    )
    (net (code "32") (name "Net-(U3-PA6)") (class "Default")
      (node (ref "R11") (pin "1") (pinfunction "1_1") (pintype "input"))
      (node (ref "U3") (pin "12") (pinfunction "PA6_12") (pintype "bidirectional"))
    )
    (net (code "33") (name "Net-(U3-PA7)") (class "Default")
      (node (ref "R12") (pin "1") (pinfunction "1_1") (pintype "input"))
      (node (ref "U3") (pin "13") (pinfunction "PA7_13") (pintype "bidirectional"))
    )
    (net (code "34") (name "Net-(U3-PA13(SWDIO))") (class "Default")
      (node (ref "CN3") (pin "2") (pinfunction "2_2") (pintype "input"))
      (node (ref "U3") (pin "19") (pinfunction "PA13(SWDIO)_19") (pintype "bidirectional"))
    )
    (net (code "35") (name "Net-(U3-PA14(SWCLK))") (class "Default")
      (node (ref "CN3") (pin "1") (pinfunction "1_1") (pintype "input"))
      (node (ref "U3") (pin "20") (pinfunction "PA14(SWCLK)_20") (pintype "bidirectional"))
    )
    (net (code "36") (name "Net-(U3-PB1)") (class "Default")
      (node (ref "R28") (pin "1") (pinfunction "1_1") (pintype "input"))
      (node (ref "R5") (pin "1") (pinfunction "1_1") (pintype "input"))
      (node (ref "U3") (pin "14") (pinfunction "PB1_14") (pintype "bidirectional"))
    )
    (net (code "37") (name "Net-(U3-PF0-OSC_IN(PF0))") (class "Default")
      (node (ref "C1") (pin "2") (pinfunction "2_2") (pintype "input"))
      (node (ref "U2") (pin "1") (pinfunction "1_1") (pintype "input"))
      (node (ref "U3") (pin "2") (pinfunction "PF0-OSC_IN(PF0)_2") (pintype "bidirectional"))
    )
    (net (code "38") (name "Net-(U3-PF1-OSC_OUT(PF1))") (class "Default")
      (node (ref "C2") (pin "2") (pinfunction "2_2") (pintype "input"))
      (node (ref "U2") (pin "3") (pinfunction "3_3") (pintype "input"))
      (node (ref "U3") (pin "3") (pinfunction "PF1-OSC_OUT(PF1)_3") (pintype "bidirectional"))
    )
    (net (code "39") (name "Net-(U4-BS)") (class "Default")
      (node (ref "C9") (pin "1") (pinfunction "1_1") (pintype "input"))
      (node (ref "U4") (pin "1") (pinfunction "BS_1") (pintype "input"))
    )
    (net (code "40") (name "Net-(U4-EN)") (class "Default")
      (node (ref "R10") (pin "1") (pinfunction "1_1") (pintype "input"))
      (node (ref "U4") (pin "4") (pinfunction "EN_4") (pintype "input"))
    )
    (net (code "41") (name "Net-(U4-FB)") (class "Default")
      (node (ref "C4") (pin "1") (pinfunction "1_1") (pintype "input"))
      (node (ref "R8") (pin "1") (pinfunction "1_1") (pintype "input"))
      (node (ref "R9") (pin "2") (pinfunction "2_2") (pintype "input"))
      (node (ref "U4") (pin "3") (pinfunction "FB_3") (pintype "input"))
    )
    (net (code "42") (name "Net-(U6-VO)") (class "Default")
      (node (ref "R6") (pin "1") (pinfunction "1_1") (pintype "input"))
      (node (ref "U6") (pin "5") (pinfunction "VO_5") (pintype "input"))
    )
    (net (code "43") (name "VCC") (class "Default")
      (node (ref "C26") (pin "2") (pinfunction "2_2") (pintype "input"))
      (node (ref "C27") (pin "2") (pinfunction "2_2") (pintype "input"))
      (node (ref "C28") (pin "2") (pinfunction "2_2") (pintype "input"))
      (node (ref "C5") (pin "2") (pinfunction "2_2") (pintype "input"))
      (node (ref "C6") (pin "2") (pinfunction "2_2") (pintype "input"))
      (node (ref "D5") (pin "1") (pinfunction "K_1") (pintype "input"))
      (node (ref "D6") (pin "1") (pinfunction "A_1") (pintype "input"))
      (node (ref "H1") (pin "1") (pinfunction "1_1") (pintype "unspecified"))
      (node (ref "H3") (pin "1") (pinfunction "1_1") (pintype "unspecified"))
      (node (ref "R10") (pin "2") (pinfunction "2_2") (pintype "input"))
      (node (ref "R20") (pin "1") (pinfunction "1_1") (pintype "input"))
      (node (ref "U4") (pin "5") (pinfunction "IN_5") (pintype "input"))
      (node (ref "U6") (pin "6") (pinfunction "VCC_6") (pintype "input"))
    )
  )
)
